# led_strip.net
KiCad netlist of a schematic drawn in EAGLE
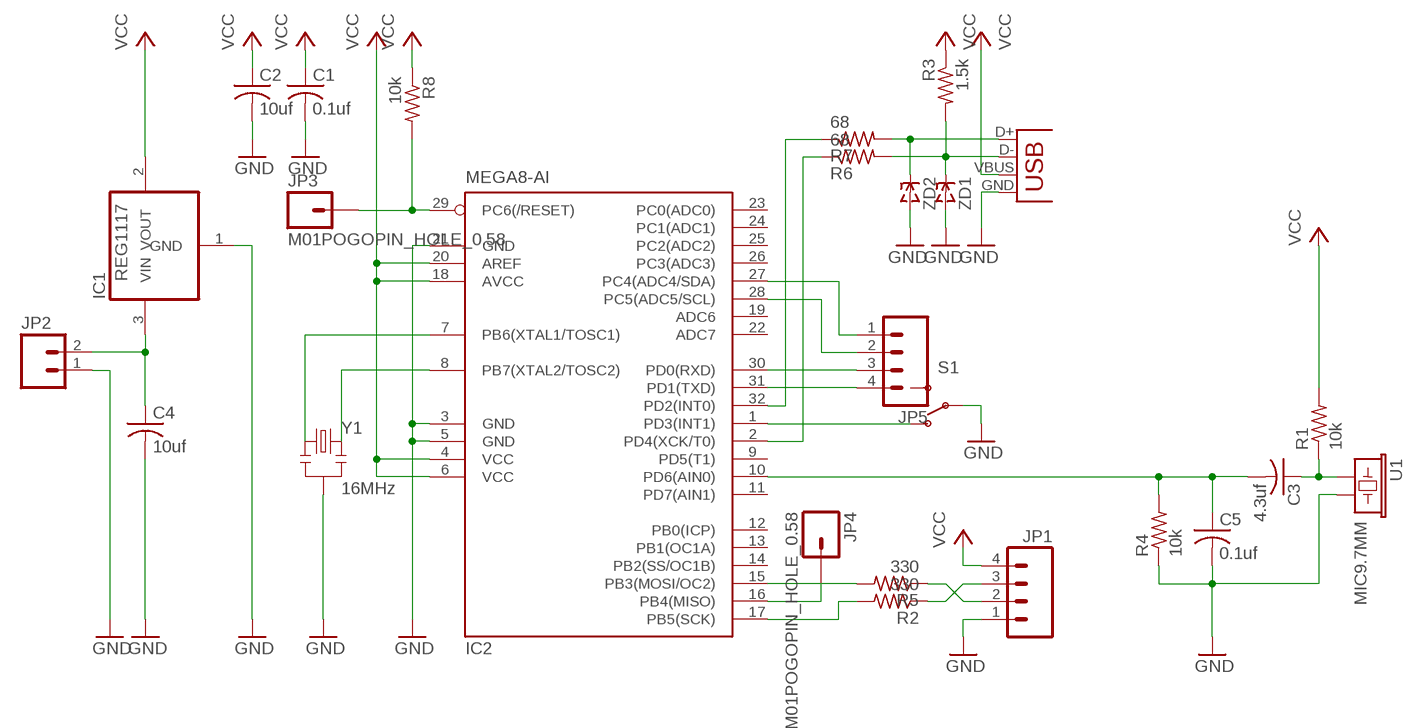
[diagram p0: schematic, sheet 1]

(export (version "E")
  (design (tool "Eeschema 10.0.6"))
  (components
    (comp (ref "C1")
      (value "0.1uf")
      (footprint "eagle-import:C0805")
      (libsource (lib "eagle-import") (part "C-USC0805"))
    )
    (comp (ref "C2")
      (value "10uf")
      (footprint "eagle-import:C0805")
      (libsource (lib "eagle-import") (part "C-USC0805"))
    )
    (comp (ref "C3")
      (value "4.3uf")
      (footprint "eagle-import:C0805")
      (libsource (lib "eagle-import") (part "C-USC0805"))
    )
    (comp (ref "C4")
      (value "10uf")
      (footprint "eagle-import:C0805")
      (libsource (lib "eagle-import") (part "C-USC0805"))
    )
    (comp (ref "C5")
      (value "0.1uf")
      (footprint "eagle-import:C0805")
      (libsource (lib "eagle-import") (part "C-USC0805"))
    )
    (comp (ref "IC1")
      (value "REG1117")
      (footprint "eagle-import:SOT223")
      (libsource (lib "eagle-import") (part "REG1117"))
    )
    (comp (ref "IC2")
      (value "MEGA8-AI")
      (footprint "eagle-import:TQFP32-08")
      (fields (field (name "MPN") "ATMEGA8-16AU"))
      (libsource (lib "eagle-import") (part "MEGA8-AI"))
    )
    (comp (ref "JP1")
      (value "M04LONGPADS")
      (footprint "eagle-import:1X04_LONGPADS")
      (libsource (lib "eagle-import") (part "M04LONGPADS"))
    )
    (comp (ref "JP2")
      (value "M02LOCK_LONGPADS")
      (footprint "eagle-import:1X02_LOCK_LONGPADS")
      (libsource (lib "eagle-import") (part "M02LOCK_LONGPADS"))
    )
    (comp (ref "JP3")
      (value "M01POGOPIN_HOLE_0.58")
      (footprint "eagle-import:1X01_POGOPIN_HOLE_0.58")
      (libsource (lib "eagle-import") (part "M01POGOPIN_HOLE_0.58"))
    )
    (comp (ref "JP4")
      (value "M01POGOPIN_HOLE_0.58")
      (footprint "eagle-import:1X01_POGOPIN_HOLE_0.58")
      (libsource (lib "eagle-import") (part "M01POGOPIN_HOLE_0.58"))
    )
    (comp (ref "JP5")
      (value "M04PTH")
      (footprint "eagle-import:1X04")
      (libsource (lib "eagle-import") (part "M04PTH"))
    )
    (comp (ref "R1")
      (value "10k")
      (footprint "eagle-import:R0805")
      (libsource (lib "eagle-import") (part "R-US_R0805"))
    )
    (comp (ref "R2")
      (value "330")
      (footprint "eagle-import:R0805")
      (libsource (lib "eagle-import") (part "R-US_R0805"))
    )
    (comp (ref "R3")
      (value "1.5k")
      (footprint "eagle-import:R0805")
      (libsource (lib "eagle-import") (part "R-US_R0805"))
    )
    (comp (ref "R4")
      (value "10k")
      (footprint "eagle-import:R0805")
      (libsource (lib "eagle-import") (part "R-US_R0805"))
    )
    (comp (ref "R5")
      (value "330")
      (footprint "eagle-import:R0805")
      (libsource (lib "eagle-import") (part "R-US_R0805"))
    )
    (comp (ref "R6")
      (value "68")
      (footprint "eagle-import:R0805")
      (libsource (lib "eagle-import") (part "R-US_R0805"))
    )
    (comp (ref "R7")
      (value "68")
      (footprint "eagle-import:R0805")
      (libsource (lib "eagle-import") (part "R-US_R0805"))
    )
    (comp (ref "R8")
      (value "10k")
      (footprint "eagle-import:R0805")
      (libsource (lib "eagle-import") (part "R-US_R0805"))
    )
    (comp (ref "S1")
      (value "SWITCH-SPSTSMD2")
      (footprint "eagle-import:SWITCH-SPDT-SMD")
      (libsource (lib "eagle-import") (part "SWITCH-SPSTSMD2"))
    )
    (comp (ref "U1")
      (value "MIC9.7MM")
      (footprint "eagle-import:MIC-9.7MM")
      (libsource (lib "eagle-import") (part "MIC9.7MM"))
    )
    (comp (ref "X1")
      (value "USB-SMD-NS")
      (footprint "eagle-import:USB-MINIB-NOSTOP")
      (libsource (lib "eagle-import") (part "USB-SMD-NS"))
    )
    (comp (ref "Y1")
      (value "16MHz")
      (footprint "eagle-import:RESONATOR-SMD")
      (libsource (lib "eagle-import") (part "RESONATORSMD"))
    )
    (comp (ref "ZD1")
      (value "ZENERSOD-323F")
      (footprint "eagle-import:SOD-323F")
      (libsource (lib "eagle-import") (part "ZENERSOD-323F"))
    )
    (comp (ref "ZD2")
      (value "ZENERSOD-323F")
      (footprint "eagle-import:SOD-323F")
      (libsource (lib "eagle-import") (part "ZENERSOD-323F"))
    )
  )
  (nets
    (net (code "1") (name "GND") (class "Default")
      (node (ref "C1") (pin "2") (pinfunction "2_2") (pintype "passive"))
      (node (ref "C2") (pin "2") (pinfunction "2_2") (pintype "passive"))
      (node (ref "C4") (pin "2") (pinfunction "2_2") (pintype "passive"))
      (node (ref "C5") (pin "2") (pinfunction "2_2") (pintype "passive"))
      (node (ref "IC1") (pin "1") (pinfunction "GND_1") (pintype "power_in"))
      (node (ref "IC2") (pin "21") (pinfunction "GND_21") (pintype "power_in"))
      (node (ref "IC2") (pin "3") (pinfunction "GND_3") (pintype "power_in"))
      (node (ref "IC2") (pin "5") (pinfunction "GND_5") (pintype "power_in"))
      (node (ref "JP1") (pin "1") (pinfunction "1_1") (pintype "passive"))
      (node (ref "JP2") (pin "1") (pinfunction "1_1") (pintype "passive"))
      (node (ref "R4") (pin "1") (pinfunction "1_1") (pintype "passive"))
      (node (ref "S1") (pin "2") (pinfunction "P_2") (pintype "passive"))
      (node (ref "U1") (pin "2") (pinfunction "2_2") (pintype "passive"))
      (node (ref "X1") (pin "GND") (pinfunction "GND_GND") (pintype "bidirectional"))
      (node (ref "Y1") (pin "2") (pinfunction "2_2") (pintype "passive"))
      (node (ref "ZD1") (pin "A") (pinfunction "A_A") (pintype "passive"))
      (node (ref "ZD2") (pin "A") (pinfunction "A_A") (pintype "passive"))
    )
    (net (code "2") (name "Net-(C3-Pad1)") (class "Default")
      (node (ref "C3") (pin "1") (pinfunction "1_1") (pintype "passive"))
      (node (ref "R1") (pin "1") (pinfunction "1_1") (pintype "passive"))
      (node (ref "U1") (pin "1") (pinfunction "1_1") (pintype "passive"))
    )
    (net (code "3") (name "Net-(IC1-VIN)") (class "Default")
      (node (ref "C4") (pin "1") (pinfunction "1_1") (pintype "passive"))
      (node (ref "IC1") (pin "3") (pinfunction "VIN_3") (pintype "input"))
      (node (ref "JP2") (pin "2") (pinfunction "2_2") (pintype "passive"))
    )
    (net (code "4") (name "Net-(IC2-PB3(MOSI{slash}OC2))") (class "Default")
      (node (ref "IC2") (pin "15") (pinfunction "PB3(MOSI/OC2)_15") (pintype "bidirectional"))
      (node (ref "R5") (pin "2") (pinfunction "2_2") (pintype "passive"))
    )
    (net (code "5") (name "Net-(IC2-PB4(MISO))") (class "Default")
      (node (ref "IC2") (pin "16") (pinfunction "PB4(MISO)_16") (pintype "bidirectional"))
      (node (ref "JP4") (pin "1") (pinfunction "1_1") (pintype "passive"))
    )
    (net (code "6") (name "Net-(IC2-PB5(SCK))") (class "Default")
      (node (ref "IC2") (pin "17") (pinfunction "PB5(SCK)_17") (pintype "bidirectional"))
      (node (ref "R2") (pin "2") (pinfunction "2_2") (pintype "passive"))
    )
    (net (code "7") (name "Net-(IC2-PB6(XTAL1{slash}TOSC1))") (class "Default")
      (node (ref "IC2") (pin "7") (pinfunction "PB6(XTAL1/TOSC1)_7") (pintype "bidirectional"))
      (node (ref "Y1") (pin "1") (pinfunction "1_1") (pintype "passive"))
    )
    (net (code "8") (name "Net-(IC2-PB7(XTAL2{slash}TOSC2))") (class "Default")
      (node (ref "IC2") (pin "8") (pinfunction "PB7(XTAL2/TOSC2)_8") (pintype "bidirectional"))
      (node (ref "Y1") (pin "3") (pinfunction "3_3") (pintype "passive"))
    )
    (net (code "9") (name "Net-(IC2-PC4(ADC4{slash}SDA))") (class "Default")
      (node (ref "IC2") (pin "27") (pinfunction "PC4(ADC4/SDA)_27") (pintype "bidirectional"))
      (node (ref "JP5") (pin "1") (pinfunction "1_1") (pintype "passive"))
    )
    (net (code "10") (name "Net-(IC2-PC5(ADC5{slash}SCL))") (class "Default")
      (node (ref "IC2") (pin "28") (pinfunction "PC5(ADC5/SCL)_28") (pintype "bidirectional"))
      (node (ref "JP5") (pin "2") (pinfunction "2_2") (pintype "passive"))
    )
    (net (code "11") (name "Net-(IC2-PC6({slash}RESET))") (class "Default")
      (node (ref "IC2") (pin "29") (pinfunction "PC6(/RESET)_29") (pintype "bidirectional"))
      (node (ref "JP3") (pin "1") (pinfunction "1_1") (pintype "passive"))
      (node (ref "R8") (pin "2") (pinfunction "2_2") (pintype "passive"))
    )
    (net (code "12") (name "Net-(IC2-PD0(RXD))") (class "Default")
      (node (ref "IC2") (pin "30") (pinfunction "PD0(RXD)_30") (pintype "bidirectional"))
      (node (ref "JP5") (pin "3") (pinfunction "3_3") (pintype "passive"))
    )
    (net (code "13") (name "Net-(IC2-PD1(TXD))") (class "Default")
      (node (ref "IC2") (pin "31") (pinfunction "PD1(TXD)_31") (pintype "bidirectional"))
      (node (ref "JP5") (pin "4") (pinfunction "4_4") (pintype "passive"))
    )
    (net (code "14") (name "Net-(IC2-PD2(INT0))") (class "Default")
      (node (ref "IC2") (pin "32") (pinfunction "PD2(INT0)_32") (pintype "bidirectional"))
      (node (ref "R7") (pin "1") (pinfunction "1_1") (pintype "passive"))
    )
    (net (code "15") (name "Net-(IC2-PD3(INT1))") (class "Default")
      (node (ref "IC2") (pin "1") (pinfunction "PD3(INT1)_1") (pintype "bidirectional"))
      (node (ref "S1") (pin "1") (pinfunction "O_1") (pintype "passive"))
    )
    (net (code "16") (name "Net-(IC2-PD4(XCK{slash}T0))") (class "Default")
      (node (ref "IC2") (pin "2") (pinfunction "PD4(XCK/T0)_2") (pintype "bidirectional"))
      (node (ref "R6") (pin "1") (pinfunction "1_1") (pintype "passive"))
    )
    (net (code "17") (name "Net-(IC2-PD6(AIN0))") (class "Default")
      (node (ref "C3") (pin "2") (pinfunction "2_2") (pintype "passive"))
      (node (ref "C5") (pin "1") (pinfunction "1_1") (pintype "passive"))
      (node (ref "IC2") (pin "10") (pinfunction "PD6(AIN0)_10") (pintype "bidirectional"))
      (node (ref "R4") (pin "2") (pinfunction "2_2") (pintype "passive"))
    )
    (net (code "18") (name "Net-(JP1-Pad2)") (class "Default")
      (node (ref "JP1") (pin "2") (pinfunction "2_2") (pintype "passive"))
      (node (ref "R5") (pin "1") (pinfunction "1_1") (pintype "passive"))
    )
    (net (code "19") (name "Net-(JP1-Pad3)") (class "Default")
      (node (ref "JP1") (pin "3") (pinfunction "3_3") (pintype "passive"))
      (node (ref "R2") (pin "1") (pinfunction "1_1") (pintype "passive"))
    )
    (net (code "20") (name "Net-(R3-Pad2)") (class "Default")
      (node (ref "R3") (pin "2") (pinfunction "2_2") (pintype "passive"))
      (node (ref "R6") (pin "2") (pinfunction "2_2") (pintype "passive"))
      (node (ref "X1") (pin "D-") (pinfunction "D-_D-") (pintype "bidirectional"))
      (node (ref "ZD1") (pin "C") (pinfunction "C_C") (pintype "passive"))
    )
    (net (code "21") (name "Net-(R7-Pad2)") (class "Default")
      (node (ref "R7") (pin "2") (pinfunction "2_2") (pintype "passive"))
      (node (ref "X1") (pin "D+") (pinfunction "D+_D+") (pintype "bidirectional"))
      (node (ref "ZD2") (pin "C") (pinfunction "C_C") (pintype "passive"))
    )
    (net (code "22") (name "VCC") (class "Default")
      (node (ref "C1") (pin "1") (pinfunction "1_1") (pintype "passive"))
      (node (ref "C2") (pin "1") (pinfunction "1_1") (pintype "passive"))
      (node (ref "IC1") (pin "2") (pinfunction "VOUT_2") (pintype "output"))
      (node (ref "IC2") (pin "18") (pinfunction "AVCC_18") (pintype "power_in"))
      (node (ref "IC2") (pin "20") (pinfunction "AREF_20") (pintype "passive"))
      (node (ref "IC2") (pin "4") (pinfunction "VCC_4") (pintype "power_in"))
      (node (ref "IC2") (pin "6") (pinfunction "VCC_6") (pintype "power_in"))
      (node (ref "JP1") (pin "4") (pinfunction "4_4") (pintype "passive"))
      (node (ref "R1") (pin "2") (pinfunction "2_2") (pintype "passive"))
      (node (ref "R3") (pin "1") (pinfunction "1_1") (pintype "passive"))
      (node (ref "R8") (pin "1") (pinfunction "1_1") (pintype "passive"))
      (node (ref "X1") (pin "VBUS") (pinfunction "VBUS_VBUS") (pintype "bidirectional"))
    )
    (net (code "23") (name "unconnected-(IC2-ADC6-Pad19)") (class "Default")
      (node (ref "IC2") (pin "19") (pinfunction "ADC6_19") (pintype "bidirectional"))
    )
    (net (code "24") (name "unconnected-(IC2-ADC7-Pad22)") (class "Default")
      (node (ref "IC2") (pin "22") (pinfunction "ADC7_22") (pintype "bidirectional"))
    )
    (net (code "25") (name "unconnected-(IC2-PB0(ICP)-Pad12)") (class "Default")
      (node (ref "IC2") (pin "12") (pinfunction "PB0(ICP)_12") (pintype "bidirectional"))
    )
    (net (code "26") (name "unconnected-(IC2-PB1(OC1A)-Pad13)") (class "Default")
      (node (ref "IC2") (pin "13") (pinfunction "PB1(OC1A)_13") (pintype "bidirectional"))
    )
    (net (code "27") (name "unconnected-(IC2-PB2(SS{slash}OC1B)-Pad14)") (class "Default")
      (node (ref "IC2") (pin "14") (pinfunction "PB2(SS/OC1B)_14") (pintype "bidirectional"))
    )
    (net (code "28") (name "unconnected-(IC2-PC0(ADC0)-Pad23)") (class "Default")
      (node (ref "IC2") (pin "23") (pinfunction "PC0(ADC0)_23") (pintype "bidirectional"))
    )
    (net (code "29") (name "unconnected-(IC2-PC1(ADC1)-Pad24)") (class "Default")
      (node (ref "IC2") (pin "24") (pinfunction "PC1(ADC1)_24") (pintype "bidirectional"))
    )
    (net (code "30") (name "unconnected-(IC2-PC2(ADC2)-Pad25)") (class "Default")
      (node (ref "IC2") (pin "25") (pinfunction "PC2(ADC2)_25") (pintype "bidirectional"))
    )
    (net (code "31") (name "unconnected-(IC2-PC3(ADC3)-Pad26)") (class "Default")
      (node (ref "IC2") (pin "26") (pinfunction "PC3(ADC3)_26") (pintype "bidirectional"))
    )
    (net (code "32") (name "unconnected-(IC2-PD5(T1)-Pad9)") (class "Default")
      (node (ref "IC2") (pin "9") (pinfunction "PD5(T1)_9") (pintype "bidirectional"))
    )
    (net (code "33") (name "unconnected-(IC2-PD7(AIN1)-Pad11)") (class "Default")
      (node (ref "IC2") (pin "11") (pinfunction "PD7(AIN1)_11") (pintype "bidirectional"))
    )
    (net (code "34") (name "unconnected-(S1-S-Pad3)") (class "Default")
      (node (ref "S1") (pin "3") (pinfunction "S_3") (pintype "passive"))
    )
  )
)
